# MicroController_Core.net
KiCad netlist of a schematic drawn in Altium Designer
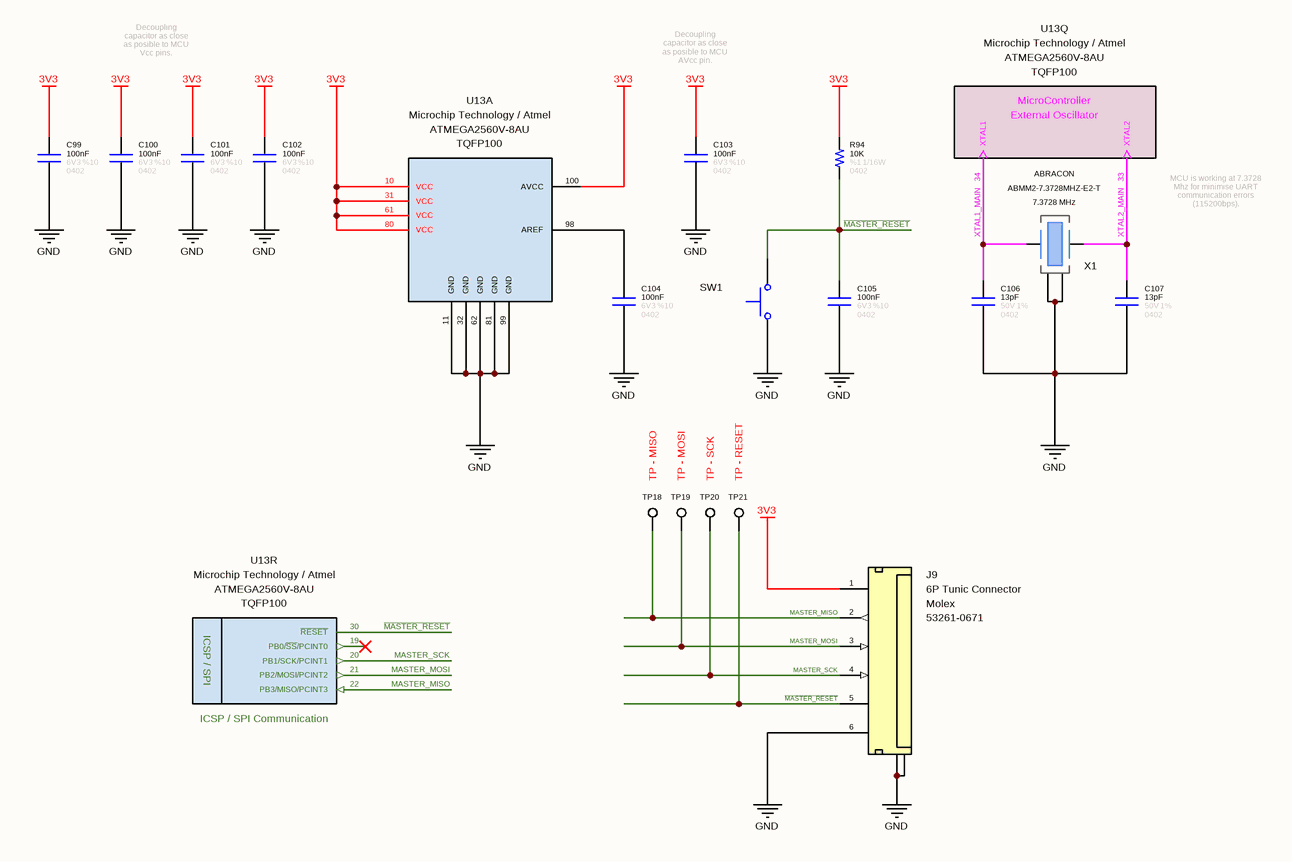
[diagram p0: MicroController Core.SchDoc]

(export (version "E")
  (design (tool "Eeschema 10.0.6"))
  (components
    (comp (ref "C99")
      (value "100nF")
      (footprint "CAPACITOR_0402")
      (description "Capacitor - 100nF [0402-6V3] (Ceramic)")
      (fields
        (field (name "MANUFACTURER PART NUMBER") "04026D104KAT4A")
        (field (name "TOLERANCE") "%10")
        (field (name "VOLTAGE") "6V3")
        (field (name "CASE") "0402")
        (field (name "Comment") "Capacitor - 100nF [0402] (Ceramic)")
      )
      (libsource (lib "Akkoyun") (part "Capacitor - 100nF [0402-6V3]"))
    )
    (comp (ref "C100")
      (value "100nF")
      (footprint "CAPACITOR_0402")
      (description "Capacitor - 100nF [0402-6V3] (Ceramic)")
      (fields
        (field (name "MANUFACTURER PART NUMBER") "04026D104KAT4A")
        (field (name "TOLERANCE") "%10")
        (field (name "VOLTAGE") "6V3")
        (field (name "CASE") "0402")
        (field (name "Comment") "Capacitor - 100nF [0402] (Ceramic)")
      )
      (libsource (lib "Akkoyun") (part "Capacitor - 100nF [0402-6V3]"))
    )
    (comp (ref "C101")
      (value "100nF")
      (footprint "CAPACITOR_0402")
      (description "Capacitor - 100nF [0402-6V3] (Ceramic)")
      (fields
        (field (name "MANUFACTURER PART NUMBER") "04026D104KAT4A")
        (field (name "TOLERANCE") "%10")
        (field (name "VOLTAGE") "6V3")
        (field (name "CASE") "0402")
        (field (name "Comment") "Capacitor - 100nF [0402] (Ceramic)")
      )
      (libsource (lib "Akkoyun") (part "Capacitor - 100nF [0402-6V3]"))
    )
    (comp (ref "C102")
      (value "100nF")
      (footprint "CAPACITOR_0402")
      (description "Capacitor - 100nF [0402-6V3] (Ceramic)")
      (fields
        (field (name "MANUFACTURER PART NUMBER") "04026D104KAT4A")
        (field (name "TOLERANCE") "%10")
        (field (name "VOLTAGE") "6V3")
        (field (name "CASE") "0402")
        (field (name "Comment") "Capacitor - 100nF [0402] (Ceramic)")
      )
      (libsource (lib "Akkoyun") (part "Capacitor - 100nF [0402-6V3]"))
    )
    (comp (ref "C103")
      (value "100nF")
      (footprint "CAPACITOR_0402")
      (description "Capacitor - 100nF [0402-6V3] (Ceramic)")
      (fields
        (field (name "MANUFACTURER PART NUMBER") "04026D104KAT4A")
        (field (name "TOLERANCE") "%10")
        (field (name "VOLTAGE") "6V3")
        (field (name "CASE") "0402")
        (field (name "Comment") "Capacitor - 100nF [0402] (Ceramic)")
      )
      (libsource (lib "Akkoyun") (part "Capacitor - 100nF [0402-6V3]"))
    )
    (comp (ref "C104")
      (value "100nF")
      (footprint "CAPACITOR_0402")
      (description "Capacitor - 100nF [0402-6V3] (Ceramic)")
      (fields
        (field (name "MANUFACTURER PART NUMBER") "04026D104KAT4A")
        (field (name "TOLERANCE") "%10")
        (field (name "VOLTAGE") "6V3")
        (field (name "CASE") "0402")
        (field (name "Comment") "Capacitor - 100nF [0402] (Ceramic)")
      )
      (libsource (lib "Akkoyun") (part "Capacitor - 100nF [0402-6V3]"))
    )
    (comp (ref "C105")
      (value "100nF")
      (footprint "CAPACITOR_0402")
      (description "Capacitor - 100nF [0402-6V3] (Ceramic)")
      (fields
        (field (name "MANUFACTURER PART NUMBER") "04026D104KAT4A")
        (field (name "TOLERANCE") "%10")
        (field (name "VOLTAGE") "6V3")
        (field (name "CASE") "0402")
        (field (name "Comment") "Capacitor - 100nF [0402] (Ceramic)")
      )
      (libsource (lib "Akkoyun") (part "Capacitor - 100nF [0402-6V3]"))
    )
    (comp (ref "C106")
      (value "13pF")
      (footprint "CAPACITOR_0402")
      (description "Multilayer Ceramic Capacitors - SMD - 50V 13pF X5R 0402 1%")
      (fields
        (field (name "MANUFACTURER PART NUMBER") "CBR04C130F5GAC")
        (field (name "TOLERANCE") "1%")
        (field (name "CASE") "0402")
        (field (name "VOLTAGE") "50V")
        (field (name "Comment") "Capacitor - 13pF [0402] (Ceramic)")
      )
      (libsource (lib "Akkoyun") (part "Capacitor - 13pF [0402-50V]"))
    )
    (comp (ref "C107")
      (value "13pF")
      (footprint "CAPACITOR_0402")
      (description "Multilayer Ceramic Capacitors - SMD - 50V 13pF X5R 0402 1%")
      (fields
        (field (name "MANUFACTURER PART NUMBER") "CBR04C130F5GAC")
        (field (name "TOLERANCE") "1%")
        (field (name "CASE") "0402")
        (field (name "VOLTAGE") "50V")
        (field (name "Comment") "Capacitor - 13pF [0402] (Ceramic)")
      )
      (libsource (lib "Akkoyun") (part "Capacitor - 13pF [0402-50V]"))
    )
    (comp (ref "J9")
      (value "6P Tunic Connector")
      (footprint "Connector_Tunic 6P")
      (description "Mini Tunic Connector with 6P")
      (fields
        (field (name "MANUFACTURER PART NUMBER") "53261-0671")
        (field (name "MANUFACTURER NAME") "Molex")
      )
      (libsource (lib "Akkoyun") (part "Connector - Mini Tunic 6P (1.25)"))
    )
    (comp (ref "R94")
      (value "10K")
      (footprint "RESISTOR_0402")
      (description "Thick Film Resistors - SMD 1/16 W 10 KOhm 1%")
      (fields
        (field (name "MANUFACTURER PART NUMBER") "CRCW040210K0FKED")
        (field (name "TOLERANCE") "%1")
        (field (name "CASE") "0402")
        (field (name "POWER") "1/16W")
        (field (name "Comment") "10K - 0402 - %1 - 1/16W")
      )
      (libsource (lib "Akkoyun") (part "Resistor - 10K [0402]"))
    )
    (comp (ref "SW1")
      (value "PTS526SK08SMTR2LFS")
      (footprint "PTS526_Switch")
      (description "Switch Tactile N.O. SPST Flush Round Button Gull Wing 0.05A 12VDC 200000Cycles 2.45N SMD T/R")
      (libsource (lib "Akkoyun") (part "Switch - Push Button"))
    )
    (comp (ref "TP18")
      (value "TP - MISO")
      (footprint "TP")
      (description "Test Point")
      (libsource (lib "Akkoyun") (part "PCB - Test Point"))
    )
    (comp (ref "TP19")
      (value "TP - MOSI")
      (footprint "TP")
      (description "Test Point")
      (libsource (lib "Akkoyun") (part "PCB - Test Point"))
    )
    (comp (ref "TP20")
      (value "TP - SCK")
      (footprint "TP")
      (description "Test Point")
      (libsource (lib "Akkoyun") (part "PCB - Test Point"))
    )
    (comp (ref "TP21")
      (value "TP - RESET")
      (footprint "TP")
      (description "Test Point")
      (libsource (lib "Akkoyun") (part "PCB - Test Point"))
    )
    (comp (ref "U13")
      (value "ATMEGA2560V-8AU")
      (footprint "TQFP-100")
      (description "ATmega Series 256 KB Flash 8 KB SRAM 8 MHz 8-Bit Microcontroller - TQFP-100")
      (fields
        (field (name "MANUFACTURER NAME") "Microchip Technology / Atmel")
        (field (name "MANUFACTURER PART NUMBER") "ATMEGA2560V-8AU")
        (field (name "CASE") "TQFP100")
      )
      (libsource (lib "Akkoyun") (part "IC - AtMega2560V-8AU"))
    )
    (comp (ref "X1")
      (value "ABMM2-7.3728MHZ-E2-T")
      (footprint "CRYSTAL - 7.3728 MHz")
      (description "CRYSTAL 7.3728MHZ 18PF SMD")
      (fields
        (field (name "MANUFACTURER NAME") "ABRACON")
        (field (name "MANUFACTURER PART NUMBER") "ABMM2-7.3728MHZ-E2-T")
        (field (name "FREQUENCY") "7.3728 MHz")
      )
      (libsource (lib "Akkoyun") (part "Crystal - 7.3728MHz"))
    )
  )
  (nets
    (net (code "1") (name "/MASTER_MISO") (class "Default")
      (node (ref "J9") (pin "2") (pinfunction "M_DRV_2") (pintype "output"))
      (node (ref "TP18") (pin "1") (pinfunction "1_1") (pintype "passive"))
      (node (ref "U13") (pin "22") (pinfunction "PB3/MISO/PCINT3_22") (pintype "input"))
    )
    (net (code "2") (name "/MASTER_MOSI") (class "Default")
      (node (ref "J9") (pin "3") (pinfunction "M_DRV_3") (pintype "input"))
      (node (ref "TP19") (pin "1") (pinfunction "1_1") (pintype "passive"))
      (node (ref "U13") (pin "21") (pinfunction "PB2/MOSI/PCINT2_21") (pintype "output"))
    )
    (net (code "3") (name "/MASTER_SCK") (class "Default")
      (node (ref "J9") (pin "4") (pinfunction "M_DRV_4") (pintype "input"))
      (node (ref "TP20") (pin "1") (pinfunction "1_1") (pintype "passive"))
      (node (ref "U13") (pin "20") (pinfunction "PB1/SCK/PCINT1_20") (pintype "output"))
    )
    (net (code "4") (name "/XTAL1_MAIN") (class "Default")
      (node (ref "C106") (pin "2") (pinfunction "2_2") (pintype "passive"))
      (node (ref "U13") (pin "34") (pinfunction "XTAL1_34") (pintype "passive"))
      (node (ref "X1") (pin "3") (pinfunction "OUT/IN_3") (pintype "passive"))
    )
    (net (code "5") (name "/XTAL2_MAIN") (class "Default")
      (node (ref "C107") (pin "2") (pinfunction "2_2") (pintype "passive"))
      (node (ref "U13") (pin "33") (pinfunction "XTAL2_33") (pintype "passive"))
      (node (ref "X1") (pin "1") (pinfunction "IN/OUT_1") (pintype "passive"))
    )
    (net (code "6") (name "/~{MASTER_RESET}") (class "Default")
      (node (ref "C105") (pin "2") (pinfunction "2_2") (pintype "passive"))
      (node (ref "J9") (pin "5") (pinfunction "M_DRV_5") (pintype "passive"))
      (node (ref "R94") (pin "1") (pinfunction "1_1") (pintype "passive"))
      (node (ref "SW1") (pin "2") (pinfunction "COM_2") (pintype "passive"))
      (node (ref "TP21") (pin "1") (pinfunction "1_1") (pintype "passive"))
      (node (ref "U13") (pin "30") (pinfunction "~{RESET}_30") (pintype "passive"))
    )
    (net (code "7") (name "3V3") (class "Default")
      (node (ref "C100") (pin "2") (pinfunction "2_2") (pintype "passive"))
      (node (ref "C101") (pin "2") (pinfunction "2_2") (pintype "passive"))
      (node (ref "C102") (pin "2") (pinfunction "2_2") (pintype "passive"))
      (node (ref "C103") (pin "2") (pinfunction "2_2") (pintype "passive"))
      (node (ref "C99") (pin "2") (pinfunction "2_2") (pintype "passive"))
      (node (ref "J9") (pin "1") (pinfunction "VBAT_1") (pintype "passive"))
      (node (ref "R94") (pin "2") (pinfunction "2_2") (pintype "passive"))
      (node (ref "U13") (pin "10") (pinfunction "VCC_10") (pintype "power_in"))
      (node (ref "U13") (pin "100") (pinfunction "AVCC_100") (pintype "passive"))
      (node (ref "U13") (pin "31") (pinfunction "VCC_31") (pintype "power_in"))
      (node (ref "U13") (pin "61") (pinfunction "VCC_61") (pintype "power_in"))
      (node (ref "U13") (pin "80") (pinfunction "VCC_80") (pintype "power_in"))
    )
    (net (code "8") (name "GND") (class "Default")
      (node (ref "C100") (pin "1") (pinfunction "1_1") (pintype "passive"))
      (node (ref "C101") (pin "1") (pinfunction "1_1") (pintype "passive"))
      (node (ref "C102") (pin "1") (pinfunction "1_1") (pintype "passive"))
      (node (ref "C103") (pin "1") (pinfunction "1_1") (pintype "passive"))
      (node (ref "C104") (pin "1") (pinfunction "1_1") (pintype "passive"))
      (node (ref "C105") (pin "1") (pinfunction "1_1") (pintype "passive"))
      (node (ref "C106") (pin "1") (pinfunction "1_1") (pintype "passive"))
      (node (ref "C107") (pin "1") (pinfunction "1_1") (pintype "passive"))
      (node (ref "C99") (pin "1") (pinfunction "1_1") (pintype "passive"))
      (node (ref "J9") (pin "6") (pinfunction "M_DRV_6") (pintype "passive"))
      (node (ref "J9") (pin "7") (pinfunction "GND_7") (pintype "passive"))
      (node (ref "J9") (pin "8") (pinfunction "GND_8") (pintype "passive"))
      (node (ref "SW1") (pin "1") (pinfunction "NC_1") (pintype "passive"))
      (node (ref "U13") (pin "11") (pinfunction "GND_11") (pintype "passive"))
      (node (ref "U13") (pin "32") (pinfunction "GND_32") (pintype "passive"))
      (node (ref "U13") (pin "62") (pinfunction "GND_62") (pintype "passive"))
      (node (ref "U13") (pin "81") (pinfunction "GND_81") (pintype "passive"))
      (node (ref "U13") (pin "99") (pinfunction "GND_99") (pintype "passive"))
      (node (ref "X1") (pin "2") (pinfunction "GND_2") (pintype "passive"))
      (node (ref "X1") (pin "4") (pinfunction "GND_4") (pintype "passive"))
    )
    (net (code "9") (name "Net-(U13A-AREF)") (class "Default")
      (node (ref "C104") (pin "2") (pinfunction "2_2") (pintype "passive"))
      (node (ref "U13") (pin "98") (pinfunction "AREF_98") (pintype "passive"))
    )
    (net (code "10") (name "unconnected-(U13R-PB0{slash}~{SS}{slash}PCINT0-Pad19)") (class "Default")
      (node (ref "U13") (pin "19") (pinfunction "PB0/~{SS}/PCINT0_19") (pintype "output+no_connect"))
    )
  )
)
